# UPDIProgrammerStick.net
KiCad netlist of a schematic drawn in EAGLE
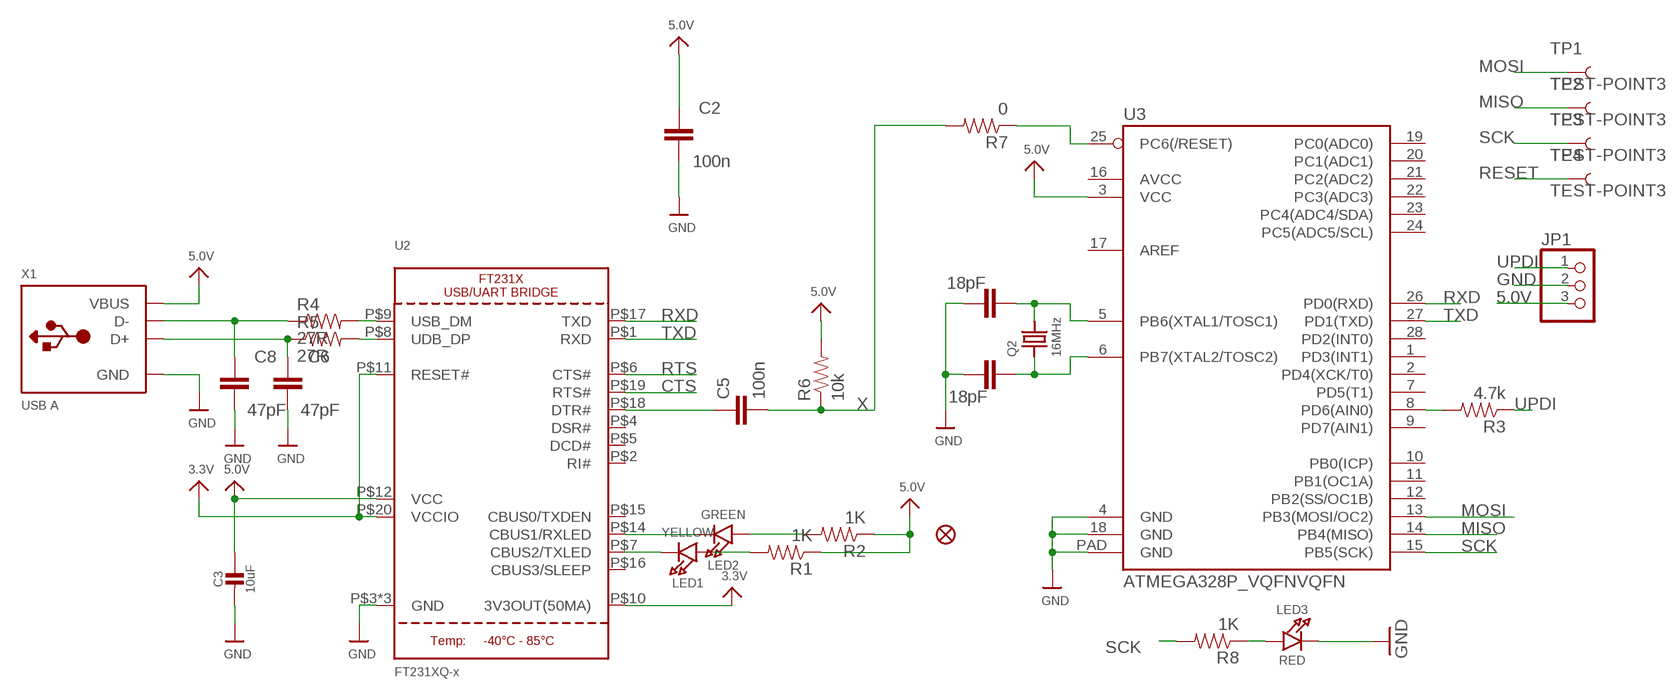
[diagram p0: schematic, sheet 1]

(export (version "E")
  (design (tool "Eeschema 10.0.6"))
  (components
    (comp (ref "C2")
      (value "100n")
      (footprint "eagle-import:0603-CAP")
      (libsource (lib "eagle-import") (part "CAP0603-CAP"))
    )
    (comp (ref "C3")
      (value "10uF")
      (footprint "eagle-import:_0805MP")
      (libsource (lib "eagle-import") (part "CAP_CERAMIC_0805MP"))
    )
    (comp (ref "C5")
      (value "100n")
      (footprint "eagle-import:0603-CAP")
      (libsource (lib "eagle-import") (part "CAP0603-CAP"))
    )
    (comp (ref "C6")
      (value "47pF")
      (footprint "eagle-import:0603-CAP")
      (libsource (lib "eagle-import") (part "CAP0603-CAP"))
    )
    (comp (ref "C8")
      (value "47pF")
      (footprint "eagle-import:0603-CAP")
      (libsource (lib "eagle-import") (part "CAP0603-CAP"))
    )
    (comp (ref "C12")
      (value "18pF")
      (footprint "eagle-import:0603-CAP")
      (libsource (lib "eagle-import") (part "CAP0603-CAP"))
    )
    (comp (ref "C13")
      (value "18pF")
      (footprint "eagle-import:0603-CAP")
      (libsource (lib "eagle-import") (part "CAP0603-CAP"))
    )
    (comp (ref "FID2")
      (value "FIDUCIAL\"\"")
      (footprint "eagle-import:FIDUCIAL_1MM")
      (libsource (lib "eagle-import") (part "FIDUCIAL{dblquote}{dblquote}"))
    )
    (comp (ref "JP1")
      (value "PINHD-1X3")
      (footprint "eagle-import:1X03")
      (libsource (lib "eagle-import") (part "PINHD-1X3"))
    )
    (comp (ref "LED1")
      (value "YELLOW")
      (footprint "eagle-import:CHIPLED_0805_NOOUTLINE")
      (libsource (lib "eagle-import") (part "LED0805_NOOUTLINE"))
    )
    (comp (ref "LED2")
      (value "GREEN")
      (footprint "eagle-import:CHIPLED_0805_NOOUTLINE")
      (libsource (lib "eagle-import") (part "LED0805_NOOUTLINE"))
    )
    (comp (ref "LED3")
      (value "RED")
      (footprint "eagle-import:CHIPLED_0805_NOOUTLINE")
      (libsource (lib "eagle-import") (part "LED0805_NOOUTLINE"))
    )
    (comp (ref "Q2")
      (value "16MHz")
      (footprint "eagle-import:CRYSTAL_3.2X2.5")
      (libsource (lib "eagle-import") (part "CRYSTALTHIN"))
    )
    (comp (ref "R1")
      (value "1K")
      (footprint "eagle-import:0805")
      (libsource (lib "eagle-import") (part "0.3OHM-1/8W-1%(0805)"))
    )
    (comp (ref "R2")
      (value "1K")
      (footprint "eagle-import:0805")
      (libsource (lib "eagle-import") (part "0.3OHM-1/8W-1%(0805)"))
    )
    (comp (ref "R3")
      (value "4.7k")
      (footprint "eagle-import:0805")
      (libsource (lib "eagle-import") (part "0.3OHM-1/8W-1%(0805)"))
    )
    (comp (ref "R4")
      (value "27R")
      (footprint "eagle-import:0805")
      (libsource (lib "eagle-import") (part "0.3OHM-1/8W-1%(0805)"))
    )
    (comp (ref "R5")
      (value "27R")
      (footprint "eagle-import:0805")
      (libsource (lib "eagle-import") (part "0.3OHM-1/8W-1%(0805)"))
    )
    (comp (ref "R6")
      (value "10k")
      (footprint "eagle-import:0805")
      (libsource (lib "eagle-import") (part "0.3OHM-1/8W-1%(0805)"))
    )
    (comp (ref "R7")
      (value "0")
      (footprint "eagle-import:0805")
      (libsource (lib "eagle-import") (part "0.3OHM-1/8W-1%(0805)"))
    )
    (comp (ref "R8")
      (value "1K")
      (footprint "eagle-import:0805")
      (libsource (lib "eagle-import") (part "0.3OHM-1/8W-1%(0805)"))
    )
    (comp (ref "TP1")
      (value "TEST-POINT3")
      (footprint "eagle-import:PAD.03X.03")
      (libsource (lib "eagle-import") (part "TEST-POINT3"))
    )
    (comp (ref "TP2")
      (value "TEST-POINT3")
      (footprint "eagle-import:PAD.03X.03")
      (libsource (lib "eagle-import") (part "TEST-POINT3"))
    )
    (comp (ref "TP3")
      (value "TEST-POINT3")
      (footprint "eagle-import:PAD.03X.03")
      (libsource (lib "eagle-import") (part "TEST-POINT3"))
    )
    (comp (ref "TP4")
      (value "TEST-POINT3")
      (footprint "eagle-import:PAD.03X.03")
      (libsource (lib "eagle-import") (part "TEST-POINT3"))
    )
    (comp (ref "U2")
      (value "FT231XQ-x")
      (footprint "eagle-import:QFN20_4MM")
      (libsource (lib "eagle-import") (part "FT231X"))
    )
    (comp (ref "U3")
      (value "ATMEGA328P_VQFNVQFN")
      (footprint "eagle-import:VQFN-28")
      (libsource (lib "eagle-import") (part "ATMEGA328P_VQFNVQFN"))
    )
    (comp (ref "X1")
      (value "USB A")
      (footprint "eagle-import:USB_A-THM")
      (libsource (lib "eagle-import") (part "USB_TYPEA_CLIENTTHM"))
    )
  )
  (nets
    (net (code "1") (name "3.3V") (class "Default")
      (node (ref "U2") (pin "P$10") (pinfunction "3V3OUT(50MA)_P$10") (pintype "power_in"))
      (node (ref "U2") (pin "P$11") (pinfunction "RESET#_P$11") (pintype "input"))
      (node (ref "U2") (pin "P$20") (pinfunction "VCCIO_P$20") (pintype "power_in"))
    )
    (net (code "2") (name "5.0V") (class "Default")
      (node (ref "C2") (pin "1") (pinfunction "1_1") (pintype "passive"))
      (node (ref "C3") (pin "1") (pinfunction "1_1") (pintype "passive"))
      (node (ref "JP1") (pin "3") (pinfunction "3_3") (pintype "passive"))
      (node (ref "R1") (pin "1") (pinfunction "1_1") (pintype "passive"))
      (node (ref "R2") (pin "1") (pinfunction "1_1") (pintype "passive"))
      (node (ref "R6") (pin "2") (pinfunction "2_2") (pintype "passive"))
      (node (ref "U2") (pin "P$12") (pinfunction "VCC_P$12") (pintype "power_in"))
      (node (ref "U3") (pin "3") (pinfunction "VCC_3") (pintype "bidirectional"))
      (node (ref "X1") (pin "VBUS") (pinfunction "VBUS_VBUS") (pintype "power_in"))
    )
    (net (code "3") (name "CTS") (class "Default")
      (node (ref "U2") (pin "P$19") (pinfunction "RTS#_P$19") (pintype "output"))
    )
    (net (code "4") (name "GND") (class "Default")
      (node (ref "C12") (pin "2") (pinfunction "2_2") (pintype "passive"))
      (node (ref "C13") (pin "2") (pinfunction "2_2") (pintype "passive"))
      (node (ref "C2") (pin "2") (pinfunction "2_2") (pintype "passive"))
      (node (ref "C3") (pin "2") (pinfunction "2_2") (pintype "passive"))
      (node (ref "C6") (pin "2") (pinfunction "2_2") (pintype "passive"))
      (node (ref "C8") (pin "2") (pinfunction "2_2") (pintype "passive"))
      (node (ref "JP1") (pin "2") (pinfunction "2_2") (pintype "passive"))
      (node (ref "LED3") (pin "C") (pinfunction "C_C") (pintype "passive"))
      (node (ref "U2") (pin "P$13") (pinfunction "GND_P$13") (pintype "power_in"))
      (node (ref "U2") (pin "P$21") (pinfunction "GND_P$21") (pintype "power_in"))
      (node (ref "U2") (pin "P$3") (pinfunction "GND_P$3") (pintype "power_in"))
      (node (ref "U3") (pin "18") (pinfunction "GND_18") (pintype "bidirectional"))
      (node (ref "U3") (pin "4") (pinfunction "GND_4") (pintype "bidirectional"))
      (node (ref "U3") (pin "PAD") (pinfunction "GND_PAD") (pintype "bidirectional"))
      (node (ref "X1") (pin "GND") (pinfunction "GND_GND") (pintype "power_in"))
    )
    (net (code "5") (name "MISO") (class "Default")
      (node (ref "TP2") (pin "P$1") (pinfunction "1_P$1") (pintype "bidirectional"))
      (node (ref "U3") (pin "14") (pinfunction "PB4(MISO)_14") (pintype "bidirectional"))
    )
    (net (code "6") (name "MOSI") (class "Default")
      (node (ref "TP1") (pin "P$1") (pinfunction "1_P$1") (pintype "bidirectional"))
      (node (ref "U3") (pin "13") (pinfunction "PB3(MOSI/OC2)_13") (pintype "bidirectional"))
    )
    (net (code "7") (name "Net-(C6-Pad1)") (class "Default")
      (node (ref "C6") (pin "1") (pinfunction "1_1") (pintype "passive"))
      (node (ref "R5") (pin "1") (pinfunction "1_1") (pintype "passive"))
      (node (ref "X1") (pin "D+") (pinfunction "D+_D+") (pintype "bidirectional"))
    )
    (net (code "8") (name "Net-(C8-Pad1)") (class "Default")
      (node (ref "C8") (pin "1") (pinfunction "1_1") (pintype "passive"))
      (node (ref "R4") (pin "1") (pinfunction "1_1") (pintype "passive"))
      (node (ref "X1") (pin "D-") (pinfunction "D-_D-") (pintype "bidirectional"))
    )
    (net (code "9") (name "Net-(LED1-PadA)") (class "Default")
      (node (ref "LED1") (pin "A") (pinfunction "A_A") (pintype "passive"))
      (node (ref "R1") (pin "2") (pinfunction "2_2") (pintype "passive"))
    )
    (net (code "10") (name "Net-(LED2-PadA)") (class "Default")
      (node (ref "LED2") (pin "A") (pinfunction "A_A") (pintype "passive"))
      (node (ref "R2") (pin "2") (pinfunction "2_2") (pintype "passive"))
    )
    (net (code "11") (name "Net-(LED3-PadA)") (class "Default")
      (node (ref "LED3") (pin "A") (pinfunction "A_A") (pintype "passive"))
      (node (ref "R8") (pin "1") (pinfunction "1_1") (pintype "passive"))
    )
    (net (code "12") (name "Net-(U2-CBUS1{slash}RXLED)") (class "Default")
      (node (ref "LED2") (pin "C") (pinfunction "C_C") (pintype "passive"))
      (node (ref "U2") (pin "P$14") (pinfunction "CBUS1/RXLED_P$14") (pintype "bidirectional"))
    )
    (net (code "13") (name "Net-(U2-CBUS2{slash}TXLED)") (class "Default")
      (node (ref "LED1") (pin "C") (pinfunction "C_C") (pintype "passive"))
      (node (ref "U2") (pin "P$7") (pinfunction "CBUS2/TXLED_P$7") (pintype "bidirectional"))
    )
    (net (code "14") (name "Net-(U2-DTR#)") (class "Default")
      (node (ref "C5") (pin "1") (pinfunction "1_1") (pintype "passive"))
      (node (ref "U2") (pin "P$18") (pinfunction "DTR#_P$18") (pintype "output"))
    )
    (net (code "15") (name "Net-(U2-UDB_DP)") (class "Default")
      (node (ref "R5") (pin "2") (pinfunction "2_2") (pintype "passive"))
      (node (ref "U2") (pin "P$8") (pinfunction "UDB_DP_P$8") (pintype "input"))
    )
    (net (code "16") (name "Net-(U2-USB_DM)") (class "Default")
      (node (ref "R4") (pin "2") (pinfunction "2_2") (pintype "passive"))
      (node (ref "U2") (pin "P$9") (pinfunction "USB_DM_P$9") (pintype "input"))
    )
    (net (code "17") (name "Net-(U3-PB6(XTAL1{slash}TOSC1))") (class "Default")
      (node (ref "C12") (pin "1") (pinfunction "1_1") (pintype "passive"))
      (node (ref "Q2") (pin "2") (pinfunction "2_2") (pintype "passive"))
      (node (ref "U3") (pin "5") (pinfunction "PB6(XTAL1/TOSC1)_5") (pintype "bidirectional"))
    )
    (net (code "18") (name "Net-(U3-PB7(XTAL2{slash}TOSC2))") (class "Default")
      (node (ref "C13") (pin "1") (pinfunction "1_1") (pintype "passive"))
      (node (ref "Q2") (pin "1") (pinfunction "1_1") (pintype "passive"))
      (node (ref "U3") (pin "6") (pinfunction "PB7(XTAL2/TOSC2)_6") (pintype "bidirectional"))
    )
    (net (code "19") (name "Net-(U3-PD6(AIN0))") (class "Default")
      (node (ref "R3") (pin "2") (pinfunction "2_2") (pintype "passive"))
      (node (ref "U3") (pin "8") (pinfunction "PD6(AIN0)_8") (pintype "bidirectional"))
    )
    (net (code "20") (name "RESET") (class "Default")
      (node (ref "R7") (pin "1") (pinfunction "1_1") (pintype "passive"))
      (node (ref "TP4") (pin "P$1") (pinfunction "1_P$1") (pintype "bidirectional"))
      (node (ref "U3") (pin "25") (pinfunction "PC6(/RESET)_25") (pintype "bidirectional"))
    )
    (net (code "21") (name "RTS") (class "Default")
      (node (ref "U2") (pin "P$6") (pinfunction "CTS#_P$6") (pintype "input"))
    )
    (net (code "22") (name "RXD") (class "Default")
      (node (ref "U2") (pin "P$17") (pinfunction "TXD_P$17") (pintype "output"))
      (node (ref "U3") (pin "26") (pinfunction "PD0(RXD)_26") (pintype "bidirectional"))
    )
    (net (code "23") (name "SCK") (class "Default")
      (node (ref "R8") (pin "2") (pinfunction "2_2") (pintype "passive"))
      (node (ref "TP3") (pin "P$1") (pinfunction "1_P$1") (pintype "bidirectional"))
      (node (ref "U3") (pin "15") (pinfunction "PB5(SCK)_15") (pintype "bidirectional"))
    )
    (net (code "24") (name "TXD") (class "Default")
      (node (ref "U2") (pin "P$1") (pinfunction "RXD_P$1") (pintype "input"))
      (node (ref "U3") (pin "27") (pinfunction "PD1(TXD)_27") (pintype "bidirectional"))
    )
    (net (code "25") (name "UPDI") (class "Default")
      (node (ref "JP1") (pin "1") (pinfunction "1_1") (pintype "passive"))
      (node (ref "R3") (pin "1") (pinfunction "1_1") (pintype "passive"))
    )
    (net (code "26") (name "X") (class "Default")
      (node (ref "C5") (pin "2") (pinfunction "2_2") (pintype "passive"))
      (node (ref "R6") (pin "1") (pinfunction "1_1") (pintype "passive"))
      (node (ref "R7") (pin "2") (pinfunction "2_2") (pintype "passive"))
    )
    (net (code "27") (name "unconnected-(U2-CBUS0{slash}TXDEN-PadP$15)") (class "Default")
      (node (ref "U2") (pin "P$15") (pinfunction "CBUS0/TXDEN_P$15") (pintype "bidirectional"))
    )
    (net (code "28") (name "unconnected-(U2-CBUS3{slash}SLEEP-PadP$16)") (class "Default")
      (node (ref "U2") (pin "P$16") (pinfunction "CBUS3/SLEEP_P$16") (pintype "bidirectional"))
    )
    (net (code "29") (name "unconnected-(U2-DCD#-PadP$5)") (class "Default")
      (node (ref "U2") (pin "P$5") (pinfunction "DCD#_P$5") (pintype "input"))
    )
    (net (code "30") (name "unconnected-(U2-DSR#-PadP$4)") (class "Default")
      (node (ref "U2") (pin "P$4") (pinfunction "DSR#_P$4") (pintype "input"))
    )
    (net (code "31") (name "unconnected-(U2-RI#-PadP$2)") (class "Default")
      (node (ref "U2") (pin "P$2") (pinfunction "RI#_P$2") (pintype "input"))
    )
    (net (code "32") (name "unconnected-(U3-AREF-Pad17)") (class "Default")
      (node (ref "U3") (pin "17") (pinfunction "AREF_17") (pintype "bidirectional"))
    )
    (net (code "33") (name "unconnected-(U3-AVCC-Pad16)") (class "Default")
      (node (ref "U3") (pin "16") (pinfunction "AVCC_16") (pintype "bidirectional"))
    )
    (net (code "34") (name "unconnected-(U3-PB0(ICP)-Pad10)") (class "Default")
      (node (ref "U3") (pin "10") (pinfunction "PB0(ICP)_10") (pintype "bidirectional"))
    )
    (net (code "35") (name "unconnected-(U3-PB1(OC1A)-Pad11)") (class "Default")
      (node (ref "U3") (pin "11") (pinfunction "PB1(OC1A)_11") (pintype "bidirectional"))
    )
    (net (code "36") (name "unconnected-(U3-PB2(SS{slash}OC1B)-Pad12)") (class "Default")
      (node (ref "U3") (pin "12") (pinfunction "PB2(SS/OC1B)_12") (pintype "bidirectional"))
    )
    (net (code "37") (name "unconnected-(U3-PC0(ADC0)-Pad19)") (class "Default")
      (node (ref "U3") (pin "19") (pinfunction "PC0(ADC0)_19") (pintype "bidirectional"))
    )
    (net (code "38") (name "unconnected-(U3-PC1(ADC1)-Pad20)") (class "Default")
      (node (ref "U3") (pin "20") (pinfunction "PC1(ADC1)_20") (pintype "bidirectional"))
    )
    (net (code "39") (name "unconnected-(U3-PC2(ADC2)-Pad21)") (class "Default")
      (node (ref "U3") (pin "21") (pinfunction "PC2(ADC2)_21") (pintype "bidirectional"))
    )
    (net (code "40") (name "unconnected-(U3-PC3(ADC3)-Pad22)") (class "Default")
      (node (ref "U3") (pin "22") (pinfunction "PC3(ADC3)_22") (pintype "bidirectional"))
    )
    (net (code "41") (name "unconnected-(U3-PC4(ADC4{slash}SDA)-Pad23)") (class "Default")
      (node (ref "U3") (pin "23") (pinfunction "PC4(ADC4/SDA)_23") (pintype "bidirectional"))
    )
    (net (code "42") (name "unconnected-(U3-PC5(ADC5{slash}SCL)-Pad24)") (class "Default")
      (node (ref "U3") (pin "24") (pinfunction "PC5(ADC5/SCL)_24") (pintype "bidirectional"))
    )
    (net (code "43") (name "unconnected-(U3-PD2(INT0)-Pad28)") (class "Default")
      (node (ref "U3") (pin "28") (pinfunction "PD2(INT0)_28") (pintype "bidirectional"))
    )
    (net (code "44") (name "unconnected-(U3-PD3(INT1)-Pad1)") (class "Default")
      (node (ref "U3") (pin "1") (pinfunction "PD3(INT1)_1") (pintype "bidirectional"))
    )
    (net (code "45") (name "unconnected-(U3-PD4(XCK{slash}T0)-Pad2)") (class "Default")
      (node (ref "U3") (pin "2") (pinfunction "PD4(XCK/T0)_2") (pintype "bidirectional"))
    )
    (net (code "46") (name "unconnected-(U3-PD5(T1)-Pad7)") (class "Default")
      (node (ref "U3") (pin "7") (pinfunction "PD5(T1)_7") (pintype "bidirectional"))
    )
    (net (code "47") (name "unconnected-(U3-PD7(AIN1)-Pad9)") (class "Default")
      (node (ref "U3") (pin "9") (pinfunction "PD7(AIN1)_9") (pintype "bidirectional"))
    )
  )
)
